# QCopterMV_PWR_Sch.net
KiCad netlist of a schematic drawn in Altium Designer
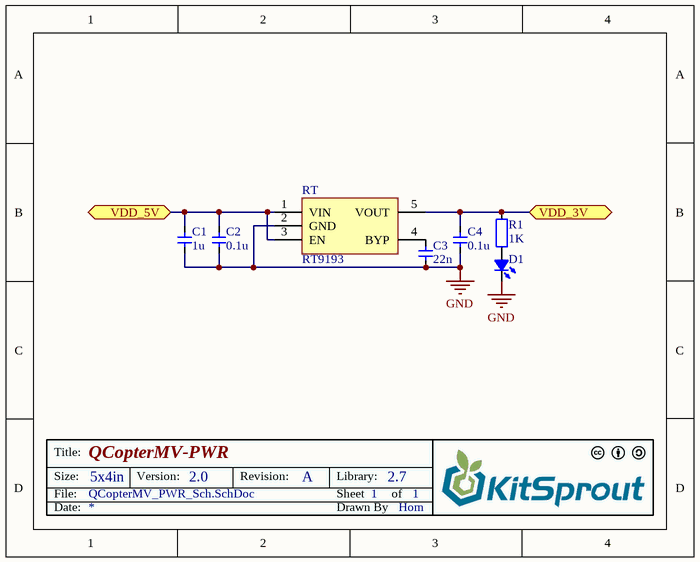
[diagram p0: QCopterMV_PWR_Sch.SchDoc]

(export (version "E")
  (design (tool "Eeschema 10.0.6"))
  (components
    (comp (ref "C1")
      (value "1u")
      (footprint "PCB_PassiveCap:CAP_0603")
      (description "Capacitor")
      (fields (field (name "Comment") "Cap_0603"))
      (libsource (lib "SCH_Passive") (part "Cap_0603"))
    )
    (comp (ref "C2")
      (value "0.1u")
      (footprint "PCB_PassiveCap:CAP_0603")
      (description "Capacitor")
      (fields (field (name "Comment") "Cap_0603"))
      (libsource (lib "SCH_Passive") (part "Cap_0603"))
    )
    (comp (ref "C3")
      (value "22n")
      (footprint "PCB_PassiveCap:CAP_0603")
      (description "Capacitor")
      (fields (field (name "Comment") "Cap_0603"))
      (libsource (lib "SCH_Passive") (part "Cap_0603"))
    )
    (comp (ref "C4")
      (value "0.1u")
      (footprint "PCB_PassiveCap:CAP_0603")
      (description "Capacitor")
      (fields (field (name "Comment") "Cap_0603"))
      (libsource (lib "SCH_Passive") (part "Cap_0603"))
    )
    (comp (ref "D1")
      (value "LED_0805")
      (footprint "PCB_ActiveLED:LED_0805_ORANGE")
      (description "LED")
      (libsource (lib "SCH_Active") (part "LED_0805"))
    )
    (comp (ref "R1")
      (value "1K")
      (footprint "PCB_PassiveRes:RES_0603")
      (description "Resistor")
      (fields (field (name "Comment") "Res_0603"))
      (libsource (lib "SCH_Passive") (part "Res_0603"))
    )
    (comp (ref "RT")
      (value "RT9193")
      (footprint "PCB_IntegratedCircuit:SOT23-5")
      (description "Power")
      (libsource (lib "SCH_IntegratedCircuit") (part "SP6205"))
    )
  )
  (nets
    (net (code "1") (name "/VDD_3V") (class "Default")
      (node (ref "C4") (pin "2") (pinfunction "2_2") (pintype "passive"))
      (node (ref "R1") (pin "2") (pinfunction "2_2") (pintype "passive"))
      (node (ref "RT") (pin "5") (pinfunction "VOUT_5") (pintype "passive"))
    )
    (net (code "2") (name "/VDD_5V") (class "Default")
      (node (ref "C1") (pin "2") (pinfunction "2_2") (pintype "passive"))
      (node (ref "C2") (pin "2") (pinfunction "2_2") (pintype "passive"))
      (node (ref "RT") (pin "1") (pinfunction "VIN_1") (pintype "passive"))
      (node (ref "RT") (pin "3") (pinfunction "EN_3") (pintype "power_in"))
    )
    (net (code "3") (name "GND") (class "Default")
      (node (ref "C1") (pin "1") (pinfunction "1_1") (pintype "passive"))
      (node (ref "C2") (pin "1") (pinfunction "1_1") (pintype "passive"))
      (node (ref "C3") (pin "2") (pinfunction "2_2") (pintype "passive"))
      (node (ref "C4") (pin "1") (pinfunction "1_1") (pintype "passive"))
      (node (ref "D1") (pin "2") (pinfunction "K_2") (pintype "passive"))
      (node (ref "RT") (pin "2") (pinfunction "GND_2") (pintype "passive"))
    )
    (net (code "4") (name "Net-(D1-A)") (class "Default")
      (node (ref "D1") (pin "1") (pinfunction "A_1") (pintype "passive"))
      (node (ref "R1") (pin "1") (pinfunction "1_1") (pintype "passive"))
    )
    (net (code "5") (name "Net-(RT-BYP)") (class "Default")
      (node (ref "C3") (pin "1") (pinfunction "1_1") (pintype "passive"))
      (node (ref "RT") (pin "4") (pinfunction "BYP_4") (pintype "passive"))
    )
  )
)
